# Sheet1.net
KiCad netlist of a schematic drawn in Altium Designer
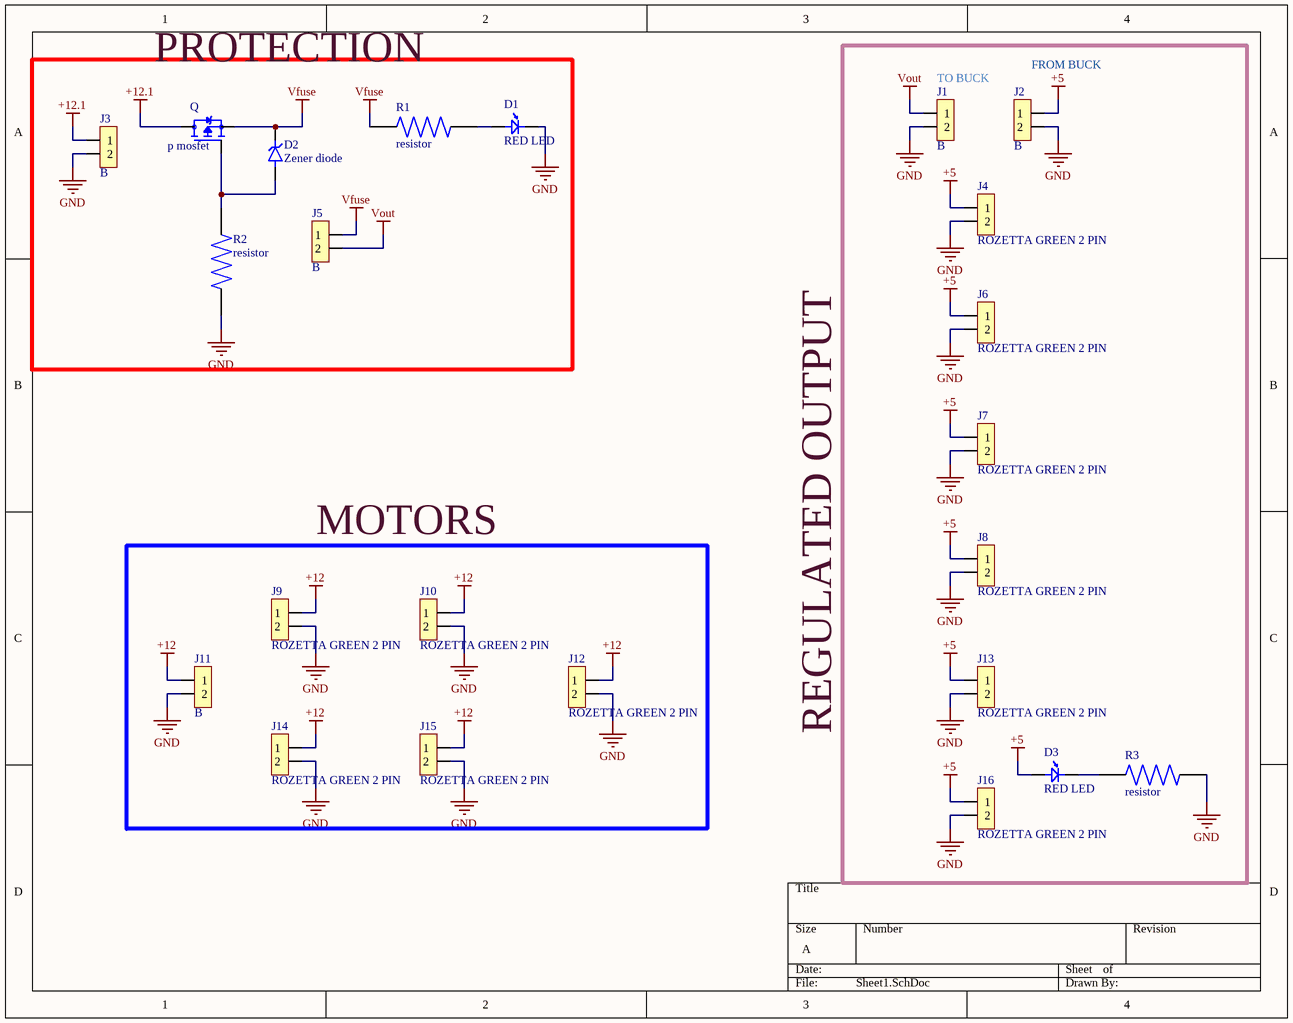
[diagram p0: Sheet1.SchDoc]

(export (version "E")
  (design (tool "Eeschema 10.0.6"))
  (components
    (comp (ref "D1")
      (value "RED LED")
      (footprint "LED_SSL-LX4673GD-LA20")
      (libsource (lib "HABROUK") (part "RED LED"))
    )
    (comp (ref "D2")
      (value "Zener diode")
      (footprint "DIOAD928W47L399D179")
      (fields (field (name "MP") "BZX55B10"))
      (libsource (lib "HABROUK") (part "Zener diode"))
    )
    (comp (ref "D3")
      (value "RED LED")
      (footprint "LED_SSL-LX4673GD-LA20")
      (libsource (lib "HABROUK") (part "RED LED"))
    )
    (comp (ref "J1")
      (value "B")
      (footprint "barrier terminal")
      (fields
        (field (name "MANUFACTURER") "DORABO")
        (field (name "MANUFACTURER PART NUMBER") "DBT50G-9.5-2P")
      )
      (libsource (lib "HABROUK") (part "barrier terminal"))
    )
    (comp (ref "J2")
      (value "B")
      (footprint "barrier terminal")
      (fields
        (field (name "MANUFACTURER") "DORABO")
        (field (name "MANUFACTURER PART NUMBER") "DBT50G-9.5-2P")
      )
      (libsource (lib "") (part "barrier terminal_1"))
    )
    (comp (ref "J3")
      (value "B")
      (footprint "barrier terminal")
      (fields
        (field (name "MANUFACTURER") "DORABO")
        (field (name "MANUFACTURER PART NUMBER") "DBT50G-9.5-2P")
      )
      (libsource (lib "HABROUK") (part "barrier terminal"))
    )
    (comp (ref "J4")
      (value "ROZETTA GREEN 2 PIN")
      (footprint "ROZETTA 2 PIN")
      (libsource (lib "") (part "ROZETTA GREEN 2 PIN_1"))
    )
    (comp (ref "J5")
      (value "B")
      (footprint "barrier terminal")
      (fields
        (field (name "MANUFACTURER") "DORABO")
        (field (name "MANUFACTURER PART NUMBER") "DBT50G-9.5-2P")
      )
      (libsource (lib "") (part "barrier terminal_1"))
    )
    (comp (ref "J6")
      (value "ROZETTA GREEN 2 PIN")
      (footprint "ROZETTA 2 PIN")
      (libsource (lib "") (part "ROZETTA GREEN 2 PIN_1"))
    )
    (comp (ref "J7")
      (value "ROZETTA GREEN 2 PIN")
      (footprint "ROZETTA 2 PIN")
      (libsource (lib "") (part "ROZETTA GREEN 2 PIN_1"))
    )
    (comp (ref "J8")
      (value "ROZETTA GREEN 2 PIN")
      (footprint "ROZETTA 2 PIN")
      (libsource (lib "") (part "ROZETTA GREEN 2 PIN_1"))
    )
    (comp (ref "J9")
      (value "ROZETTA GREEN 2 PIN")
      (footprint "ROZETTA 2 PIN")
      (libsource (lib "HABROUK") (part "ROZETTA GREEN 2 PIN"))
    )
    (comp (ref "J10")
      (value "ROZETTA GREEN 2 PIN")
      (footprint "ROZETTA 2 PIN")
      (libsource (lib "HABROUK") (part "ROZETTA GREEN 2 PIN"))
    )
    (comp (ref "J11")
      (value "B")
      (footprint "barrier terminal")
      (fields
        (field (name "MANUFACTURER") "DORABO")
        (field (name "MANUFACTURER PART NUMBER") "DBT50G-9.5-2P")
      )
      (libsource (lib "HABROUK") (part "barrier terminal"))
    )
    (comp (ref "J12")
      (value "ROZETTA GREEN 2 PIN")
      (footprint "ROZETTA 2 PIN")
      (libsource (lib "HABROUK") (part "ROZETTA GREEN 2 PIN"))
    )
    (comp (ref "J13")
      (value "ROZETTA GREEN 2 PIN")
      (footprint "ROZETTA 2 PIN")
      (libsource (lib "") (part "ROZETTA GREEN 2 PIN_1"))
    )
    (comp (ref "J14")
      (value "ROZETTA GREEN 2 PIN")
      (footprint "ROZETTA 2 PIN")
      (libsource (lib "HABROUK") (part "ROZETTA GREEN 2 PIN"))
    )
    (comp (ref "J15")
      (value "ROZETTA GREEN 2 PIN")
      (footprint "ROZETTA 2 PIN")
      (libsource (lib "HABROUK") (part "ROZETTA GREEN 2 PIN"))
    )
    (comp (ref "J16")
      (value "ROZETTA GREEN 2 PIN")
      (footprint "ROZETTA 2 PIN")
      (libsource (lib "") (part "ROZETTA GREEN 2 PIN_1"))
    )
    (comp (ref "Q")
      (value "p mosfet")
      (footprint "HABROUK:TO254P1054X469X2933-3")
      (description "P-Channel 100V 38A _Tc_ 3.1W _Ta_, 170W _Tc_ Surface Mount D2PAK")
      (fields (field (name "MF") "Infineon Technologies") (field (name "MP") "IRF5210"))
      (libsource (lib "HABROUK") (part "p mosfet"))
    )
    (comp (ref "R1")
      (value "resistor")
      (footprint "RESAD1081W64L635D269")
      (description "Resistor,Metal Film, ERC-55 100K 1% T-2 RNC55H1003FR B14 ¦ Vishay Dale RNC55H1003FRB14")
      (fields (field (name "MF") "Vishay") (field (name "MP") "RNC55H1003FRB14"))
      (libsource (lib "HABROUK") (part "resistor"))
    )
    (comp (ref "R2")
      (value "resistor")
      (footprint "RESAD1081W64L635D269")
      (description "Resistor,Metal Film, ERC-55 100K 1% T-2 RNC55H1003FR B14 ¦ Vishay Dale RNC55H1003FRB14")
      (fields (field (name "MF") "Vishay") (field (name "MP") "RNC55H1003FRB14"))
      (libsource (lib "HABROUK") (part "resistor"))
    )
    (comp (ref "R3")
      (value "resistor")
      (footprint "RESAD1081W64L635D269")
      (description "Resistor,Metal Film, ERC-55 100K 1% T-2 RNC55H1003FR B14 ¦ Vishay Dale RNC55H1003FRB14")
      (fields (field (name "MF") "Vishay") (field (name "MP") "RNC55H1003FRB14"))
      (libsource (lib "HABROUK") (part "resistor"))
    )
  )
  (nets
    (net (code "1") (name "+5") (class "Default")
      (node (ref "D3") (pin "1") (pinfunction "1_1") (pintype "passive"))
      (node (ref "J13") (pin "1") (pinfunction "1_1") (pintype "power_in"))
      (node (ref "J16") (pin "1") (pinfunction "1_1") (pintype "power_in"))
      (node (ref "J2") (pin "1") (pinfunction "1_1") (pintype "power_in"))
      (node (ref "J4") (pin "1") (pinfunction "1_1") (pintype "power_in"))
      (node (ref "J6") (pin "1") (pinfunction "1_1") (pintype "power_in"))
      (node (ref "J7") (pin "1") (pinfunction "1_1") (pintype "power_in"))
      (node (ref "J8") (pin "1") (pinfunction "1_1") (pintype "power_in"))
    )
    (net (code "2") (name "+12") (class "Default")
      (node (ref "J10") (pin "1") (pinfunction "1_1") (pintype "power_in"))
      (node (ref "J11") (pin "1") (pinfunction "1_1") (pintype "power_in"))
      (node (ref "J12") (pin "1") (pinfunction "1_1") (pintype "power_in"))
      (node (ref "J14") (pin "1") (pinfunction "1_1") (pintype "power_in"))
      (node (ref "J15") (pin "1") (pinfunction "1_1") (pintype "power_in"))
      (node (ref "J9") (pin "1") (pinfunction "1_1") (pintype "power_in"))
    )
    (net (code "3") (name "+12.1") (class "Default")
      (node (ref "J3") (pin "1") (pinfunction "1_1") (pintype "power_in"))
      (node (ref "Q") (pin "2") (pinfunction "D_2") (pintype "passive"))
    )
    (net (code "4") (name "GND") (class "Default")
      (node (ref "D1") (pin "2") (pinfunction "2_2") (pintype "passive"))
      (node (ref "J1") (pin "2") (pinfunction "2_2") (pintype "power_in"))
      (node (ref "J10") (pin "2") (pinfunction "2_2") (pintype "power_in"))
      (node (ref "J11") (pin "2") (pinfunction "2_2") (pintype "power_in"))
      (node (ref "J12") (pin "2") (pinfunction "2_2") (pintype "power_in"))
      (node (ref "J13") (pin "2") (pinfunction "2_2") (pintype "power_in"))
      (node (ref "J14") (pin "2") (pinfunction "2_2") (pintype "power_in"))
      (node (ref "J15") (pin "2") (pinfunction "2_2") (pintype "power_in"))
      (node (ref "J16") (pin "2") (pinfunction "2_2") (pintype "power_in"))
      (node (ref "J2") (pin "2") (pinfunction "2_2") (pintype "power_in"))
      (node (ref "J3") (pin "2") (pinfunction "2_2") (pintype "power_in"))
      (node (ref "J4") (pin "2") (pinfunction "2_2") (pintype "power_in"))
      (node (ref "J6") (pin "2") (pinfunction "2_2") (pintype "power_in"))
      (node (ref "J7") (pin "2") (pinfunction "2_2") (pintype "power_in"))
      (node (ref "J8") (pin "2") (pinfunction "2_2") (pintype "power_in"))
      (node (ref "J9") (pin "2") (pinfunction "2_2") (pintype "power_in"))
      (node (ref "R2") (pin "1") (pinfunction "1_1") (pintype "passive"))
      (node (ref "R3") (pin "2") (pinfunction "2_2") (pintype "passive"))
    )
    (net (code "5") (name "Net-(D1-Pad1)") (class "Default")
      (node (ref "D1") (pin "1") (pinfunction "1_1") (pintype "passive"))
      (node (ref "R1") (pin "2") (pinfunction "2_2") (pintype "passive"))
    )
    (net (code "6") (name "Net-(D3-Pad2)") (class "Default")
      (node (ref "D3") (pin "2") (pinfunction "2_2") (pintype "passive"))
      (node (ref "R3") (pin "1") (pinfunction "1_1") (pintype "passive"))
    )
    (net (code "7") (name "Net-(Q-G)") (class "Default")
      (node (ref "D2") (pin "A") (pinfunction "A_A") (pintype "passive"))
      (node (ref "Q") (pin "1") (pinfunction "G_1") (pintype "passive"))
      (node (ref "R2") (pin "2") (pinfunction "2_2") (pintype "passive"))
    )
    (net (code "8") (name "Vfuse") (class "Default")
      (node (ref "D2") (pin "C") (pinfunction "K_C") (pintype "passive"))
      (node (ref "J5") (pin "1") (pinfunction "1_1") (pintype "power_in"))
      (node (ref "Q") (pin "3") (pinfunction "S_3") (pintype "passive"))
      (node (ref "R1") (pin "1") (pinfunction "1_1") (pintype "passive"))
    )
    (net (code "9") (name "Vout") (class "Default")
      (node (ref "J1") (pin "1") (pinfunction "1_1") (pintype "power_in"))
      (node (ref "J5") (pin "2") (pinfunction "2_2") (pintype "power_in"))
    )
  )
)
